# WCH_hairDrierBOTTOM_COM_V1_5.net
KiCad netlist of a schematic drawn in Altium Designer
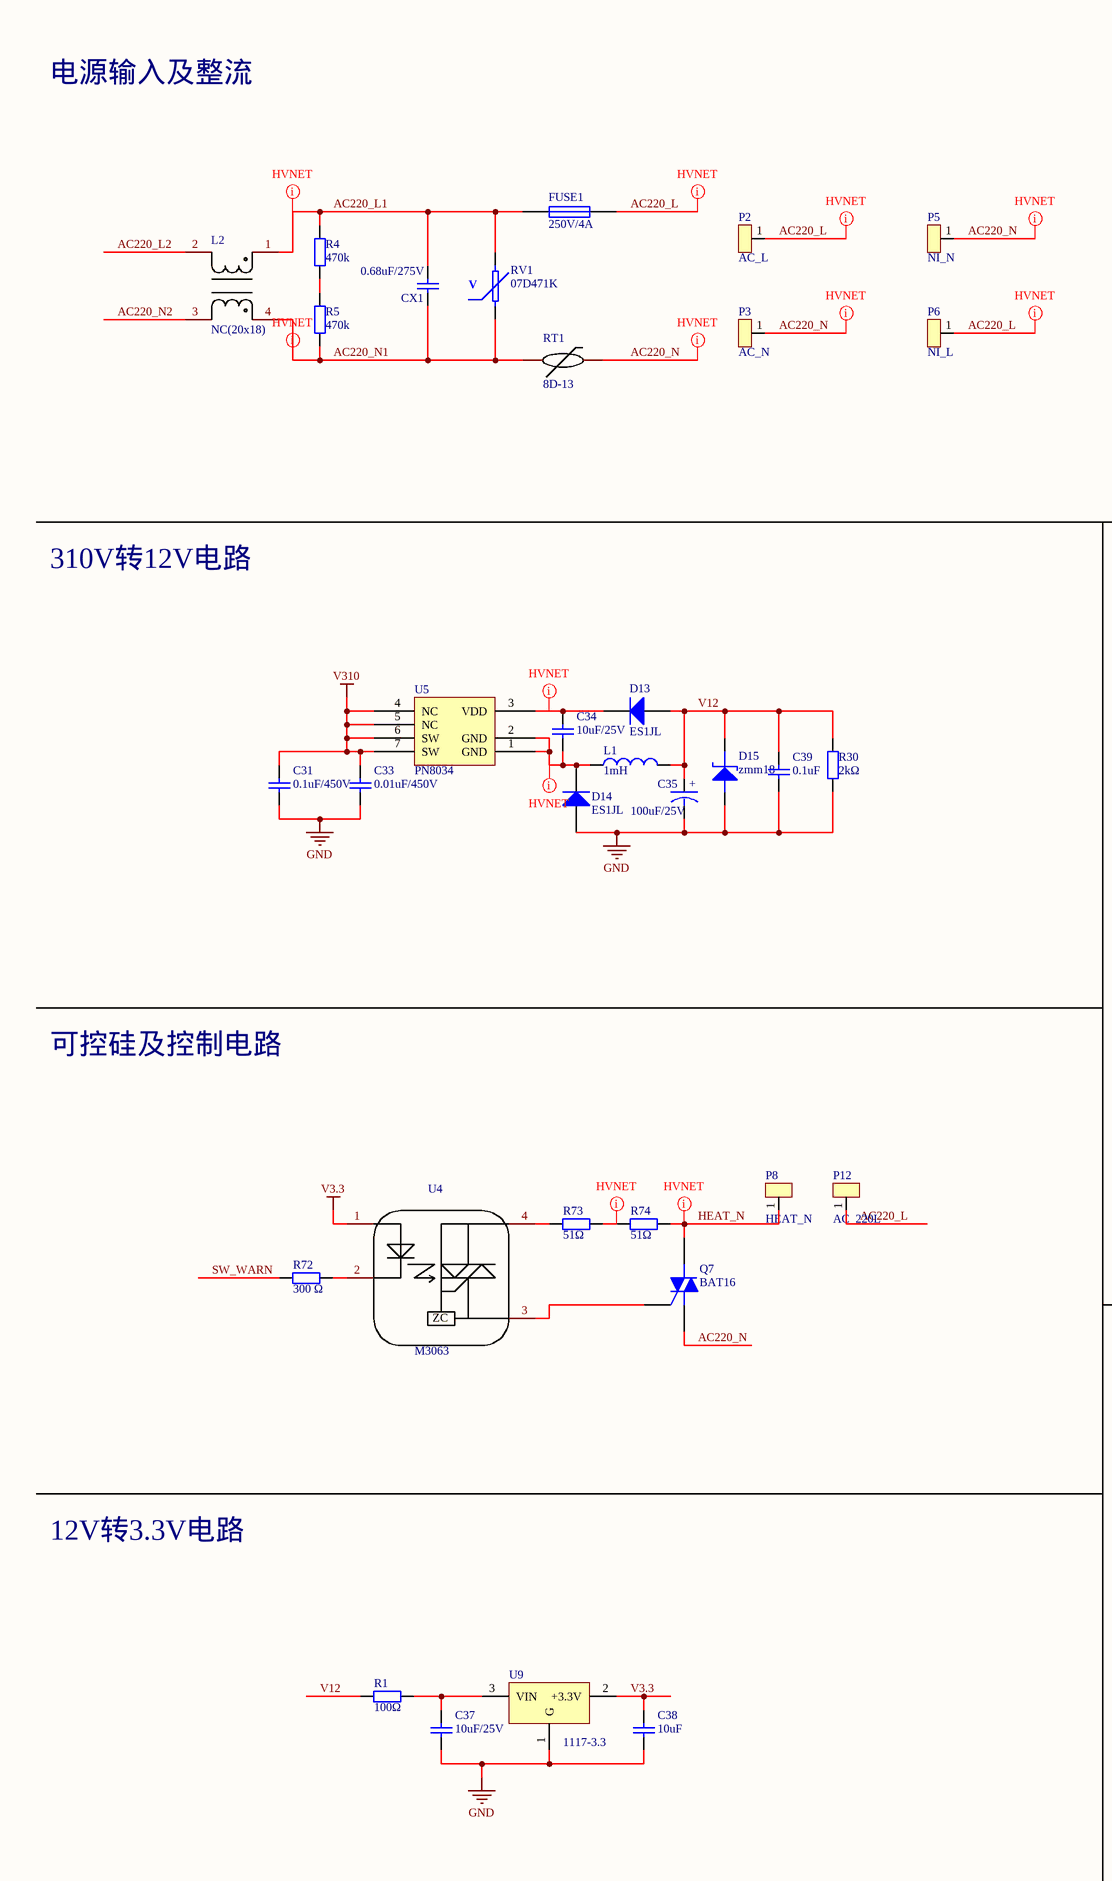
[diagram p0: WCH_hairDrierBOTTOM_COM_V1.5.SchDoc, left]
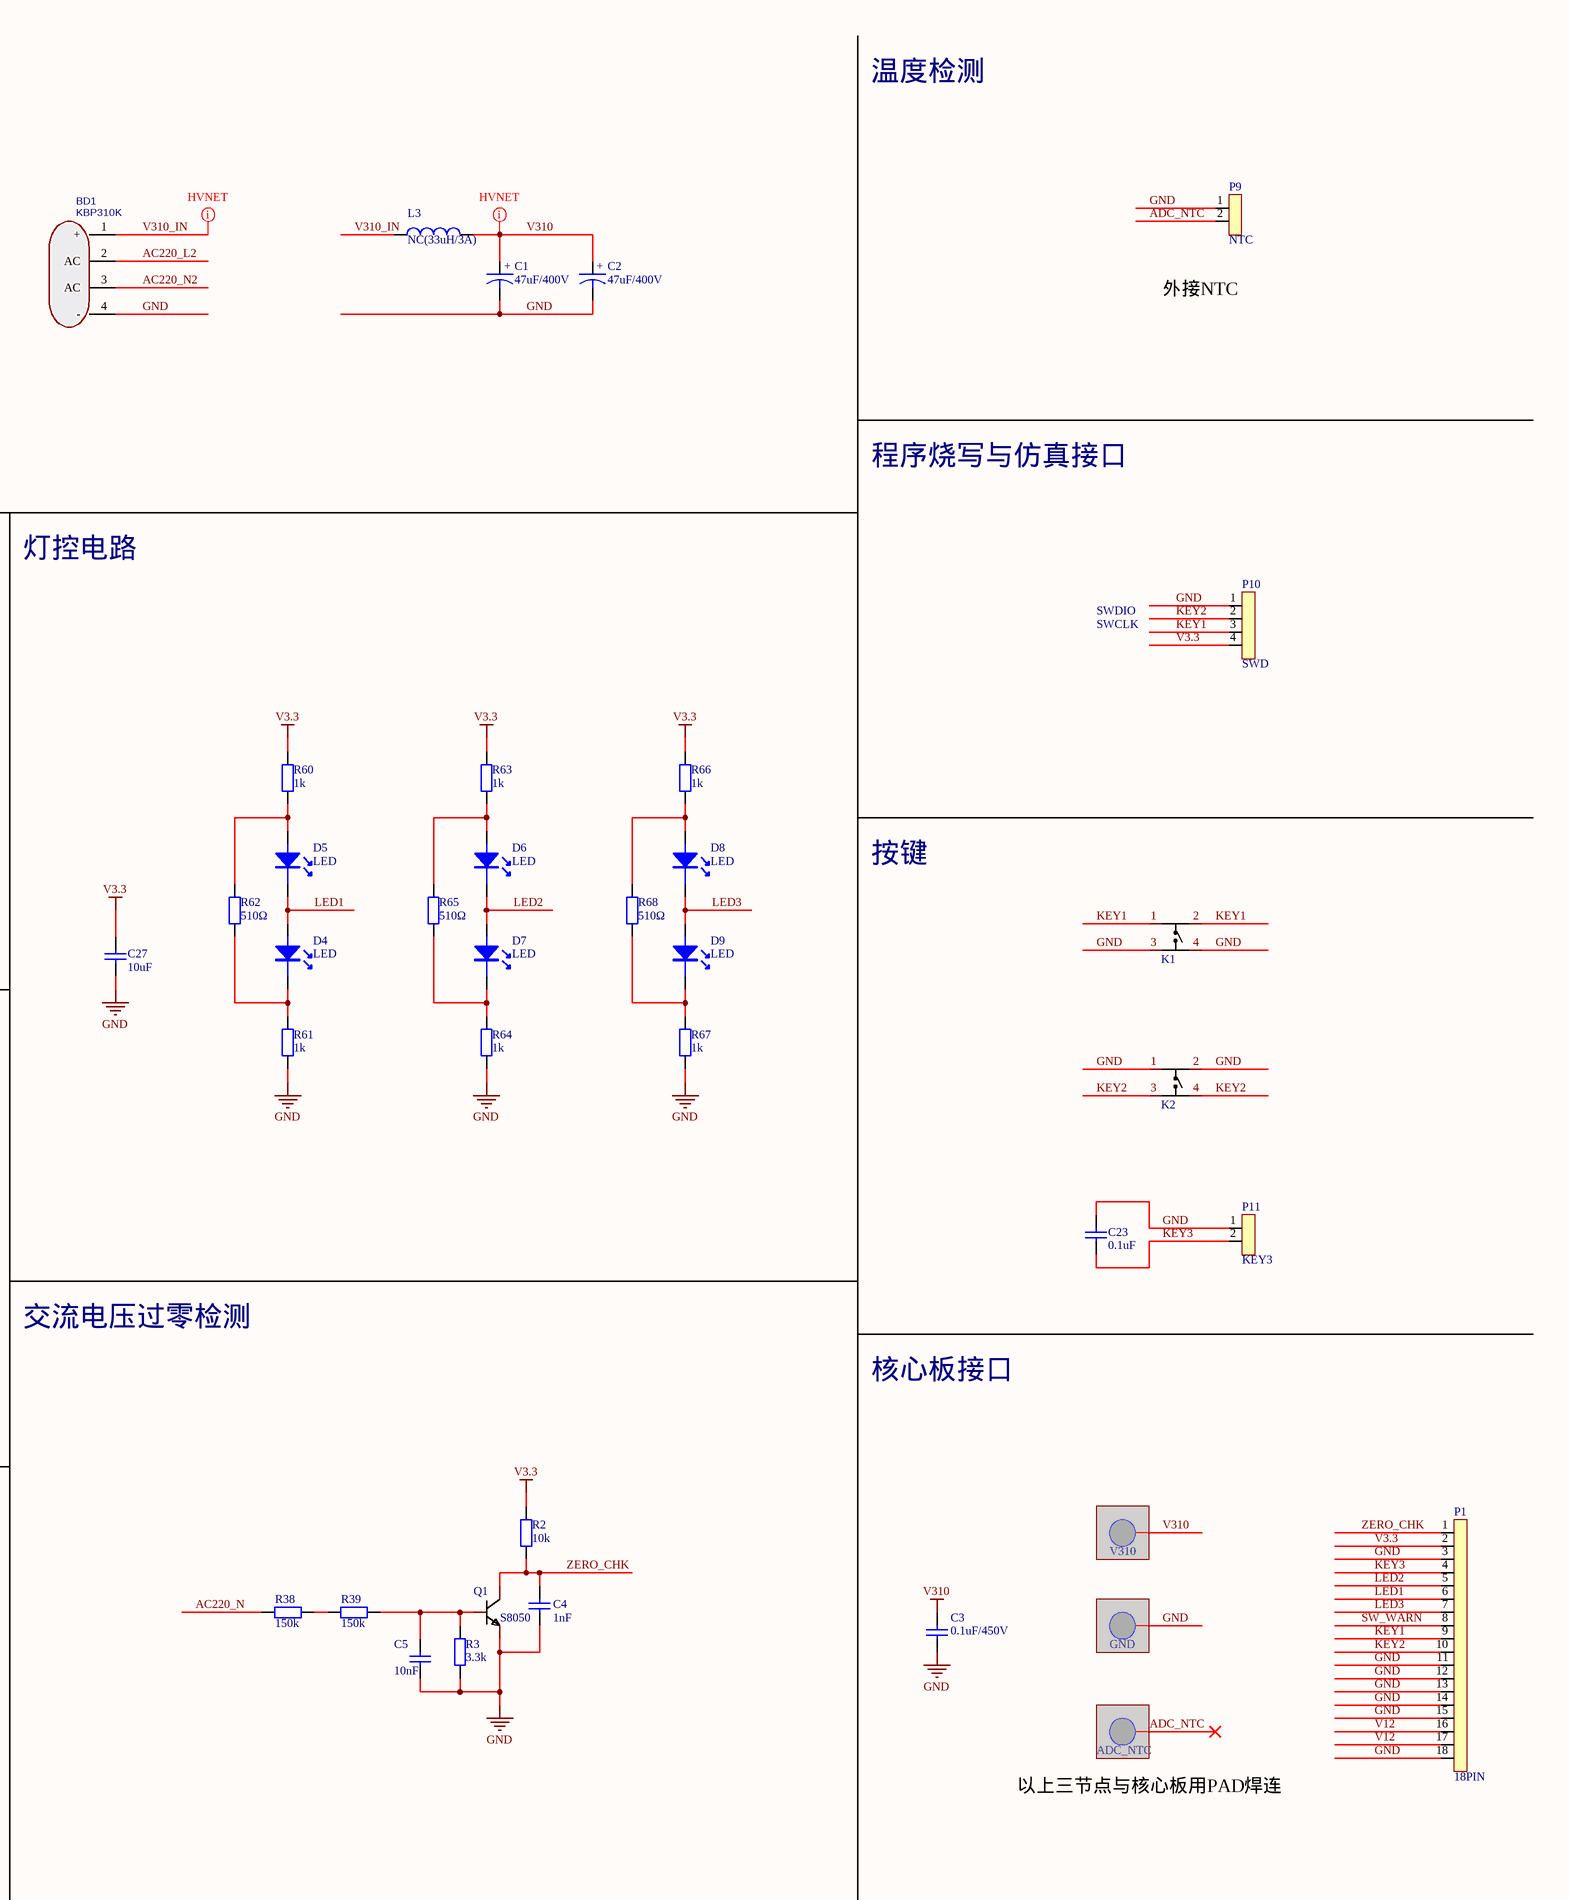
[diagram p1: WCH_hairDrierBOTTOM_COM_V1.5.SchDoc, right]

(export (version "E")
  (design (tool "Eeschema 10.0.6"))
  (components
    (comp (ref "BD1")
      (value "KBP310K")
      (footprint "3KBP")
      (fields (field (name "BOM_SUPPLIER PART") "C2496"))
      (libsource (lib "altium-import") (part "root_0_KBP310K_"))
    )
    (comp (ref "C1")
      (value "47uF/400V")
      (footprint "RB-.2/.4-M")
      (description "Capacitor")
      (libsource (lib "SMARTCORTEX M3-1700_1") (part "CAPACITOR POL_2"))
    )
    (comp (ref "C2")
      (value "47uF/400V")
      (footprint "RB-.2/.4-M")
      (description "Capacitor")
      (libsource (lib "SMARTCORTEX M3-1700_1") (part "CAPACITOR POL_2"))
    )
    (comp (ref "C3")
      (value "0.1uF/450V")
      (footprint "1206")
      (description "Capacitor (Semiconductor SIM Model)")
      (fields (field (name "PUBLISHER") "Altium Limited"))
      (libsource (lib "Miscellaneous Devices") (part "Cap Semi"))
    )
    (comp (ref "C4")
      (value "1nF")
      (footprint "M_C0402-")
      (description "Capacitor (Semiconductor SIM Model)")
      (fields (field (name "PUBLISHER") "Altium Limited"))
      (libsource (lib "Miscellaneous Devices") (part "Cap Semi"))
    )
    (comp (ref "C5")
      (value "10nF")
      (footprint "M_C0402-")
      (description "Capacitor (Semiconductor SIM Model)")
      (fields (field (name "PUBLISHER") "Altium Limited"))
      (libsource (lib "Miscellaneous Devices") (part "Cap Semi"))
    )
    (comp (ref "C23")
      (value "0.1uF")
      (footprint "M_C0402-")
      (description "Capacitor (Semiconductor SIM Model)")
      (fields (field (name "PUBLISHER") "Altium Limited"))
      (libsource (lib "Miscellaneous Devices") (part "Cap Semi"))
    )
    (comp (ref "C27")
      (value "10uF")
      (footprint "0603C")
      (description "Capacitor (Semiconductor SIM Model)")
      (fields (field (name "PUBLISHER") "Altium Limited"))
      (libsource (lib "Miscellaneous Devices") (part "Cap Semi"))
    )
    (comp (ref "C31")
      (value "0.1uF/450V")
      (footprint "1206")
      (description "Capacitor (Semiconductor SIM Model)")
      (fields (field (name "PUBLISHER") "Altium Limited"))
      (libsource (lib "Miscellaneous Devices") (part "Cap Semi"))
    )
    (comp (ref "C33")
      (value "0.01uF/450V")
      (footprint "1206")
      (description "Capacitor (Semiconductor SIM Model)")
      (fields (field (name "PUBLISHER") "Altium Limited"))
      (libsource (lib "Miscellaneous Devices") (part "Cap Semi"))
    )
    (comp (ref "C34")
      (value "10uF/25V")
      (footprint "0603C")
      (description "Capacitor (Semiconductor SIM Model)")
      (fields (field (name "PUBLISHER") "Altium Limited"))
      (libsource (lib "Miscellaneous Devices") (part "Cap Semi"))
    )
    (comp (ref "C35")
      (value "100uF/25V")
      (footprint "RB-.1/.2")
      (description "Capacitor")
      (libsource (lib "SMARTCORTEX M3-1700_1") (part "CAPACITOR POL_2"))
    )
    (comp (ref "C37")
      (value "10uF/25V")
      (footprint "0603C")
      (description "Capacitor (Semiconductor SIM Model)")
      (fields (field (name "PUBLISHER") "Altium Limited"))
      (libsource (lib "Miscellaneous Devices") (part "Cap Semi"))
    )
    (comp (ref "C38")
      (value "10uF")
      (footprint "0603C")
      (description "Capacitor (Semiconductor SIM Model)")
      (fields (field (name "PUBLISHER") "Altium Limited"))
      (libsource (lib "Miscellaneous Devices") (part "Cap Semi"))
    )
    (comp (ref "C39")
      (value "0.1uF")
      (footprint "M_C0402-")
      (description "Capacitor (Semiconductor SIM Model)")
      (fields (field (name "PUBLISHER") "Altium Limited"))
      (libsource (lib "Miscellaneous Devices") (part "Cap Semi"))
    )
    (comp (ref "CX1")
      (value "0.68uF/275V")
      (footprint "CAP-HV-10NF275V-680uf10mm")
      (description "Capacitor")
      (fields (field (name "PUBLISHER") "Altium Limited"))
      (libsource (lib "*") (part "Cap"))
    )
    (comp (ref "D4") (value "LED") (footprint "LED-0603") (libsource (lib "SUNWIN_SCH") (part "LED")))
    (comp (ref "D5") (value "LED") (footprint "LED-0603") (libsource (lib "SUNWIN_SCH") (part "LED")))
    (comp (ref "D6") (value "LED") (footprint "LED-0603") (libsource (lib "SUNWIN_SCH") (part "LED")))
    (comp (ref "D7") (value "LED") (footprint "LED-0603") (libsource (lib "SUNWIN_SCH") (part "LED")))
    (comp (ref "D8") (value "LED") (footprint "LED-0603") (libsource (lib "SUNWIN_SCH") (part "LED")))
    (comp (ref "D9") (value "LED") (footprint "LED-0603") (libsource (lib "SUNWIN_SCH") (part "LED")))
    (comp (ref "D13")
      (value "ES1JL")
      (footprint "SOD-123")
      (description "High Conductance Fast Diode")
      (fields (field (name "PUBLISHER") "Altium Limited"))
      (libsource (lib "Miscellaneous Devices") (part "Diode 1N4148"))
    )
    (comp (ref "D14")
      (value "ES1JL")
      (footprint "SOD-123")
      (description "High Conductance Fast Diode")
      (fields (field (name "PUBLISHER") "Altium Limited"))
      (libsource (lib "Miscellaneous Devices") (part "Diode 1N4148"))
    )
    (comp (ref "D15")
      (value "zmm18")
      (footprint "SOD-323")
      (libsource (lib "SUNWIN_SCH") (part "DIODE_ZENER"))
    )
    (comp (ref "FUSE1") (value "250V/4A") (footprint "FUSE_SMD") (libsource (lib "SUNWIN_SCH") (part "FUSE")))
    (comp (ref "K1")
      (value "KH-6X6X8H-STM")
      (footprint "KEY2-SMD")
      (libsource (lib "altium-import") (part "root_0_KH-6X6X8H-STM_"))
    )
    (comp (ref "K2")
      (value "KH-6X6X8H-STM")
      (footprint "KEY2-SMD")
      (libsource (lib "altium-import") (part "root_0_KH-6X6X8H-STM_"))
    )
    (comp (ref "L1")
      (value "1mH")
      (footprint "INDUCTOR-5040")
      (libsource (lib "SUNWIN_SCH") (part "INDUCTOR"))
    )
    (comp (ref "L2")
      (value "NC(20x18)")
      (footprint "M_COMM_INDUCTOR11*8")
      (fields (field (name "MANUFACTURER PART") "UU9.8-5mH"))
      (libsource (lib "altium-import") (part "root_0_mirrored_UU9.8-5mH_"))
    )
    (comp (ref "L3")
      (value "NC(33uH/3A)")
      (footprint "INDUCTOR PCMC063T")
      (libsource (lib "SUNWIN_SCH") (part "INDUCTOR"))
    )
    (comp (ref "P1") (value "18PIN") (footprint "P1.27-18-SMD") (libsource (lib "SUNWIN_SCH") (part "18PIN")))
    (comp (ref "P2")
      (value "AC_L")
      (footprint "PAD-1.2/2")
      (description "CONNECTOR")
      (libsource (lib "") (part "1PIN_1"))
    )
    (comp (ref "P3")
      (value "AC_N")
      (footprint "PAD-1.2/2")
      (description "CONNECTOR")
      (libsource (lib "") (part "1PIN_1"))
    )
    (comp (ref "P5")
      (value "NI_N")
      (footprint "PAD-1.2/2")
      (description "CONNECTOR")
      (libsource (lib "") (part "1PIN_1"))
    )
    (comp (ref "P6")
      (value "NI_L")
      (footprint "PAD-1.2/2")
      (description "CONNECTOR")
      (libsource (lib "") (part "1PIN_1"))
    )
    (comp (ref "P8")
      (value "HEAT_N")
      (footprint "PAD-1.2/2")
      (description "CONNECTOR")
      (libsource (lib "SUNWIN_SCH") (part "1PIN"))
    )
    (comp (ref "P9") (value "NTC") (footprint "GH1.25-2P") (libsource (lib "SUNWIN_SCH") (part "2PIN")))
    (comp (ref "P10") (value "SWD") (footprint "2510-4") (libsource (lib "SUNWIN_SCH") (part "4PIN")))
    (comp (ref "P11") (value "KEY3") (footprint "GH1.25-2P") (libsource (lib "SUNWIN_SCH") (part "2PIN")))
    (comp (ref "P12")
      (value "AC_220L")
      (footprint "PAD-1.2/2")
      (description "CONNECTOR")
      (libsource (lib "SUNWIN_SCH") (part "1PIN"))
    )
    (comp (ref "Q1")
      (value "S8050")
      (footprint "SOT-23")
      (libsource (lib "altium-import") (part "root_0_S8050_C105433_"))
    )
    (comp (ref "Q7")
      (value "BAT16")
      (footprint "M_TO220_2")
      (description "Silicon Bidirectional Triode Thyristor")
      (fields (field (name "PUBLISHER") "Altium Limited"))
      (libsource (lib "Miscellaneous Devices") (part "Triac"))
    )
    (comp (ref "R1")
      (value "100Ω")
      (footprint "1206-")
      (description "Resistor")
      (fields (field (name "PUBLISHER") "Altium Limited"))
      (libsource (lib "") (part "Res2_1"))
    )
    (comp (ref "R2")
      (value "10k")
      (footprint "M_R0402")
      (description "Resistor")
      (fields (field (name "PUBLISHER") "Altium Limited"))
      (libsource (lib "Miscellaneous Devices") (part "Res2"))
    )
    (comp (ref "R3")
      (value "3.3k")
      (footprint "M_R0402")
      (description "Resistor")
      (fields (field (name "PUBLISHER") "Altium Limited"))
      (libsource (lib "") (part "Res2_2"))
    )
    (comp (ref "R4")
      (value "470k")
      (footprint "1206-")
      (description "Resistor")
      (fields (field (name "PUBLISHER") "Altium Limited"))
      (libsource (lib "Miscellaneous Devices") (part "Res2"))
    )
    (comp (ref "R5")
      (value "470k")
      (footprint "1206-")
      (description "Resistor")
      (fields (field (name "PUBLISHER") "Altium Limited"))
      (libsource (lib "Miscellaneous Devices") (part "Res2"))
    )
    (comp (ref "R30")
      (value "2kΩ")
      (footprint "0805")
      (description "Resistor")
      (fields (field (name "PUBLISHER") "Altium Limited"))
      (libsource (lib "") (part "Res2_2"))
    )
    (comp (ref "R38")
      (value "150k")
      (footprint "1206-")
      (description "Resistor")
      (fields (field (name "PUBLISHER") "Altium Limited"))
      (libsource (lib "") (part "Res2_1"))
    )
    (comp (ref "R39")
      (value "150k")
      (footprint "1206-")
      (description "Resistor")
      (fields (field (name "PUBLISHER") "Altium Limited"))
      (libsource (lib "") (part "Res2_1"))
    )
    (comp (ref "R60")
      (value "1k")
      (footprint "0603")
      (description "Resistor")
      (fields (field (name "PUBLISHER") "Altium Limited"))
      (libsource (lib "") (part "Res2_2"))
    )
    (comp (ref "R61")
      (value "1k")
      (footprint "0603")
      (description "Resistor")
      (fields (field (name "PUBLISHER") "Altium Limited"))
      (libsource (lib "Miscellaneous Devices") (part "Res2"))
    )
    (comp (ref "R62")
      (value "510Ω")
      (footprint "0603")
      (description "Resistor")
      (fields (field (name "PUBLISHER") "Altium Limited"))
      (libsource (lib "Miscellaneous Devices") (part "Res2"))
    )
    (comp (ref "R63")
      (value "1k")
      (footprint "0603")
      (description "Resistor")
      (fields (field (name "PUBLISHER") "Altium Limited"))
      (libsource (lib "") (part "Res2_2"))
    )
    (comp (ref "R64")
      (value "1k")
      (footprint "0603")
      (description "Resistor")
      (fields (field (name "PUBLISHER") "Altium Limited"))
      (libsource (lib "Miscellaneous Devices") (part "Res2"))
    )
    (comp (ref "R65")
      (value "510Ω")
      (footprint "0603")
      (description "Resistor")
      (fields (field (name "PUBLISHER") "Altium Limited"))
      (libsource (lib "Miscellaneous Devices") (part "Res2"))
    )
    (comp (ref "R66")
      (value "1k")
      (footprint "0603")
      (description "Resistor")
      (fields (field (name "PUBLISHER") "Altium Limited"))
      (libsource (lib "") (part "Res2_2"))
    )
    (comp (ref "R67")
      (value "1k")
      (footprint "0603")
      (description "Resistor")
      (fields (field (name "PUBLISHER") "Altium Limited"))
      (libsource (lib "Miscellaneous Devices") (part "Res2"))
    )
    (comp (ref "R68")
      (value "510Ω")
      (footprint "0603")
      (description "Resistor")
      (fields (field (name "PUBLISHER") "Altium Limited"))
      (libsource (lib "Miscellaneous Devices") (part "Res2"))
    )
    (comp (ref "R72")
      (value "300 Ω")
      (footprint "0603")
      (description "Resistor")
      (fields (field (name "PUBLISHER") "Altium Limited"))
      (libsource (lib "") (part "Res2_1"))
    )
    (comp (ref "R73")
      (value "51Ω")
      (footprint "1206-")
      (description "Resistor")
      (fields (field (name "PUBLISHER") "Altium Limited"))
      (libsource (lib "") (part "Res2_1"))
    )
    (comp (ref "R74")
      (value "51Ω")
      (footprint "1206-")
      (description "Resistor")
      (fields (field (name "PUBLISHER") "Altium Limited"))
      (libsource (lib "") (part "Res2_1"))
    )
    (comp (ref "RT1")
      (value "8D-13")
      (footprint "RT_5D")
      (fields (field (name "MANUFACTURER PART") "NTC 5D-11"))
      (libsource (lib "altium-import") (part "root_2_NTC 5D-11_"))
    )
    (comp (ref "RV1") (value "07D471K") (footprint "7D391") (libsource (lib "SUNWIN_SCH") (part "RV")))
    (comp (ref "U4")
      (value "M3063")
      (footprint "SOP-4_L3.8-W4.6-H2.0-LS7.0-P2.54")
      (fields (field (name "MANUFACTURER PART") "FODM3063"))
      (libsource (lib "altium-import") (part "root_0_FODM3063_"))
    )
    (comp (ref "U5")
      (value "PN8034")
      (footprint "SOP-7")
      (libsource (lib "altium-import") (part "root_0_PN8054_"))
    )
    (comp (ref "U9") (value "1117-3.3") (footprint "SOT-89") (libsource (lib "SUNWIN_SCH") (part "1117-3.3")))
  )
  (nets
    (net (code "1") (name "/AC220_L") (class "Default")
      (node (ref "FUSE1") (pin "2") (pinfunction "2_2") (pintype "passive"))
      (node (ref "P12") (pin "1") (pintype "passive"))
      (node (ref "P2") (pin "1") (pintype "passive"))
      (node (ref "P6") (pin "1") (pintype "passive"))
    )
    (net (code "2") (name "/AC220_L1") (class "Default")
      (node (ref "CX1") (pin "1") (pinfunction "1_1") (pintype "passive"))
      (node (ref "FUSE1") (pin "1") (pinfunction "1_1") (pintype "passive"))
      (node (ref "L2") (pin "1") (pinfunction "1_1") (pintype "passive"))
      (node (ref "R4") (pin "1") (pinfunction "1_1") (pintype "passive"))
      (node (ref "RV1") (pin "2") (pinfunction "2_2") (pintype "passive"))
    )
    (net (code "3") (name "/AC220_L2") (class "Default")
      (node (ref "BD1") (pin "2") (pinfunction "AC_2") (pintype "passive"))
      (node (ref "L2") (pin "2") (pinfunction "2_2") (pintype "passive"))
    )
    (net (code "4") (name "/AC220_N") (class "Default")
      (node (ref "P3") (pin "1") (pintype "passive"))
      (node (ref "P5") (pin "1") (pintype "passive"))
      (node (ref "Q7") (pin "1") (pinfunction "M1_1") (pintype "passive"))
      (node (ref "R38") (pin "2") (pinfunction "2_2") (pintype "passive"))
      (node (ref "RT1") (pin "1") (pinfunction "1_1") (pintype "passive"))
    )
    (net (code "5") (name "/AC220_N1") (class "Default")
      (node (ref "CX1") (pin "2") (pinfunction "2_2") (pintype "passive"))
      (node (ref "L2") (pin "4") (pinfunction "4_4") (pintype "passive"))
      (node (ref "R5") (pin "2") (pinfunction "2_2") (pintype "passive"))
      (node (ref "RT1") (pin "2") (pinfunction "2_2") (pintype "passive"))
      (node (ref "RV1") (pin "1") (pinfunction "1_1") (pintype "passive"))
    )
    (net (code "6") (name "/AC220_N2") (class "Default")
      (node (ref "BD1") (pin "3") (pinfunction "AC_3") (pintype "passive"))
      (node (ref "L2") (pin "3") (pinfunction "3_3") (pintype "passive"))
    )
    (net (code "7") (name "/ADC_NTC") (class "Default")
      (node (ref "P9") (pin "2") (pintype "passive+no_connect"))
    )
    (net (code "8") (name "/HEAT_N") (class "Default")
      (node (ref "P8") (pin "1") (pintype "passive"))
      (node (ref "Q7") (pin "2") (pinfunction "M2_2") (pintype "passive"))
      (node (ref "R74") (pin "1") (pinfunction "1_1") (pintype "passive"))
    )
    (net (code "9") (name "/KEY1") (class "Default")
      (node (ref "K1") (pin "1") (pinfunction "A_1") (pintype "passive"))
      (node (ref "K1") (pin "2") (pinfunction "B_2") (pintype "passive"))
      (node (ref "P1") (pin "9") (pintype "passive"))
      (node (ref "P10") (pin "3") (pintype "passive"))
    )
    (net (code "10") (name "/KEY2") (class "Default")
      (node (ref "K2") (pin "3") (pinfunction "C_3") (pintype "passive"))
      (node (ref "K2") (pin "4") (pinfunction "D_4") (pintype "passive"))
      (node (ref "P1") (pin "10") (pintype "passive"))
      (node (ref "P10") (pin "2") (pintype "passive"))
    )
    (net (code "11") (name "/KEY3") (class "Default")
      (node (ref "C23") (pin "1") (pinfunction "1_1") (pintype "passive"))
      (node (ref "P1") (pin "4") (pintype "passive"))
      (node (ref "P11") (pin "2") (pintype "passive"))
    )
    (net (code "12") (name "/LED1") (class "Default")
      (node (ref "D4") (pin "1") (pinfunction "A_1") (pintype "passive"))
      (node (ref "D5") (pin "2") (pinfunction "K_2") (pintype "passive"))
      (node (ref "P1") (pin "6") (pintype "passive"))
    )
    (net (code "13") (name "/LED2") (class "Default")
      (node (ref "D6") (pin "2") (pinfunction "K_2") (pintype "passive"))
      (node (ref "D7") (pin "1") (pinfunction "A_1") (pintype "passive"))
      (node (ref "P1") (pin "5") (pintype "passive"))
    )
    (net (code "14") (name "/LED3") (class "Default")
      (node (ref "D8") (pin "2") (pinfunction "K_2") (pintype "passive"))
      (node (ref "D9") (pin "1") (pinfunction "A_1") (pintype "passive"))
      (node (ref "P1") (pin "7") (pintype "passive"))
    )
    (net (code "15") (name "/SW_WARN") (class "Default")
      (node (ref "P1") (pin "8") (pintype "passive"))
      (node (ref "R72") (pin "2") (pinfunction "2_2") (pintype "passive"))
    )
    (net (code "16") (name "/V12") (class "Default")
      (node (ref "C35") (pin "1") (pinfunction "1_1") (pintype "passive"))
      (node (ref "C39") (pin "1") (pinfunction "1_1") (pintype "passive"))
      (node (ref "D13") (pin "1") (pinfunction "A_1") (pintype "passive"))
      (node (ref "D15") (pin "2") (pinfunction "K_2") (pintype "passive"))
      (node (ref "L1") (pin "2") (pinfunction "2_2") (pintype "passive"))
      (node (ref "P1") (pin "16") (pintype "passive"))
      (node (ref "P1") (pin "17") (pintype "passive"))
      (node (ref "R1") (pin "2") (pinfunction "2_2") (pintype "passive"))
      (node (ref "R30") (pin "2") (pinfunction "2_2") (pintype "passive"))
    )
    (net (code "17") (name "/V310_IN") (class "Default")
      (node (ref "BD1") (pin "1") (pinfunction "+_1") (pintype "passive"))
      (node (ref "L3") (pin "1") (pinfunction "1_1") (pintype "passive"))
    )
    (net (code "18") (name "/ZERO_CHK") (class "Default")
      (node (ref "C4") (pin "1") (pinfunction "1_1") (pintype "passive"))
      (node (ref "P1") (pin "1") (pintype "passive"))
      (node (ref "Q1") (pin "3") (pinfunction "3_3") (pintype "passive"))
      (node (ref "R2") (pin "2") (pinfunction "2_2") (pintype "passive"))
    )
    (net (code "19") (name "GND") (class "Default")
      (node (ref "BD1") (pin "4") (pinfunction "-_4") (pintype "passive"))
      (node (ref "C1") (pin "2") (pinfunction "2_2") (pintype "passive"))
      (node (ref "C2") (pin "2") (pinfunction "2_2") (pintype "passive"))
      (node (ref "C23") (pin "2") (pinfunction "2_2") (pintype "passive"))
      (node (ref "C27") (pin "2") (pinfunction "2_2") (pintype "passive"))
      (node (ref "C3") (pin "2") (pinfunction "2_2") (pintype "passive"))
      (node (ref "C31") (pin "2") (pinfunction "2_2") (pintype "passive"))
      (node (ref "C33") (pin "2") (pinfunction "2_2") (pintype "passive"))
      (node (ref "C35") (pin "2") (pinfunction "2_2") (pintype "passive"))
      (node (ref "C37") (pin "2") (pinfunction "2_2") (pintype "passive"))
      (node (ref "C38") (pin "2") (pinfunction "2_2") (pintype "passive"))
      (node (ref "C39") (pin "2") (pinfunction "2_2") (pintype "passive"))
      (node (ref "C4") (pin "2") (pinfunction "2_2") (pintype "passive"))
      (node (ref "C5") (pin "2") (pinfunction "2_2") (pintype "passive"))
      (node (ref "D14") (pin "1") (pinfunction "A_1") (pintype "passive"))
      (node (ref "D15") (pin "1") (pinfunction "A_1") (pintype "passive"))
      (node (ref "K1") (pin "3") (pinfunction "C_3") (pintype "passive"))
      (node (ref "K1") (pin "4") (pinfunction "D_4") (pintype "passive"))
      (node (ref "K2") (pin "1") (pinfunction "A_1") (pintype "passive"))
      (node (ref "K2") (pin "2") (pinfunction "B_2") (pintype "passive"))
      (node (ref "P1") (pin "11") (pintype "passive"))
      (node (ref "P1") (pin "12") (pintype "passive"))
      (node (ref "P1") (pin "13") (pintype "passive"))
      (node (ref "P1") (pin "14") (pintype "passive"))
      (node (ref "P1") (pin "15") (pintype "passive"))
      (node (ref "P1") (pin "18") (pintype "passive"))
      (node (ref "P1") (pin "3") (pintype "passive"))
      (node (ref "P10") (pin "1") (pintype "passive"))
      (node (ref "P11") (pin "1") (pintype "passive"))
      (node (ref "P9") (pin "1") (pintype "passive"))
      (node (ref "Q1") (pin "2") (pinfunction "2_2") (pintype "passive"))
      (node (ref "R3") (pin "1") (pinfunction "1_1") (pintype "passive"))
      (node (ref "R30") (pin "1") (pinfunction "1_1") (pintype "passive"))
      (node (ref "R61") (pin "2") (pinfunction "2_2") (pintype "passive"))
      (node (ref "R64") (pin "2") (pinfunction "2_2") (pintype "passive"))
      (node (ref "R67") (pin "2") (pinfunction "2_2") (pintype "passive"))
      (node (ref "U9") (pin "1") (pinfunction "G_1") (pintype "passive"))
    )
    (net (code "20") (name "Net-(C5-Pad1)") (class "Default")
      (node (ref "C5") (pin "1") (pinfunction "1_1") (pintype "passive"))
      (node (ref "Q1") (pin "1") (pinfunction "1_1") (pintype "passive"))
      (node (ref "R3") (pin "2") (pinfunction "2_2") (pintype "passive"))
      (node (ref "R39") (pin "1") (pinfunction "1_1") (pintype "passive"))
    )
    (net (code "21") (name "Net-(D4-K)") (class "Default")
      (node (ref "D4") (pin "2") (pinfunction "K_2") (pintype "passive"))
      (node (ref "R61") (pin "1") (pinfunction "1_1") (pintype "passive"))
      (node (ref "R62") (pin "2") (pinfunction "2_2") (pintype "passive"))
    )
    (net (code "22") (name "Net-(D5-A)") (class "Default")
      (node (ref "D5") (pin "1") (pinfunction "A_1") (pintype "passive"))
      (node (ref "R60") (pin "1") (pinfunction "1_1") (pintype "passive"))
      (node (ref "R62") (pin "1") (pinfunction "1_1") (pintype "passive"))
    )
    (net (code "23") (name "Net-(D6-A)") (class "Default")
      (node (ref "D6") (pin "1") (pinfunction "A_1") (pintype "passive"))
      (node (ref "R63") (pin "1") (pinfunction "1_1") (pintype "passive"))
      (node (ref "R65") (pin "1") (pinfunction "1_1") (pintype "passive"))
    )
    (net (code "24") (name "Net-(D7-K)") (class "Default")
      (node (ref "D7") (pin "2") (pinfunction "K_2") (pintype "passive"))
      (node (ref "R64") (pin "1") (pinfunction "1_1") (pintype "passive"))
      (node (ref "R65") (pin "2") (pinfunction "2_2") (pintype "passive"))
    )
    (net (code "25") (name "Net-(D8-A)") (class "Default")
      (node (ref "D8") (pin "1") (pinfunction "A_1") (pintype "passive"))
      (node (ref "R66") (pin "1") (pinfunction "1_1") (pintype "passive"))
      (node (ref "R68") (pin "1") (pinfunction "1_1") (pintype "passive"))
    )
    (net (code "26") (name "Net-(D9-K)") (class "Default")
      (node (ref "D9") (pin "2") (pinfunction "K_2") (pintype "passive"))
      (node (ref "R67") (pin "1") (pinfunction "1_1") (pintype "passive"))
      (node (ref "R68") (pin "2") (pinfunction "2_2") (pintype "passive"))
    )
    (net (code "27") (name "Net-(D13-K)") (class "Default")
      (node (ref "C34") (pin "1") (pinfunction "1_1") (pintype "passive"))
      (node (ref "D13") (pin "2") (pinfunction "K_2") (pintype "passive"))
      (node (ref "U5") (pin "3") (pinfunction "VDD_3") (pintype "passive"))
    )
    (net (code "28") (name "Net-(D14-K)") (class "Default")
      (node (ref "C34") (pin "2") (pinfunction "2_2") (pintype "passive"))
      (node (ref "D14") (pin "2") (pinfunction "K_2") (pintype "passive"))
      (node (ref "L1") (pin "1") (pinfunction "1_1") (pintype "passive"))
      (node (ref "U5") (pin "1") (pinfunction "GND_1") (pintype "passive"))
      (node (ref "U5") (pin "2") (pinfunction "GND_2") (pintype "passive"))
    )
    (net (code "29") (name "Net-(Q7-G)") (class "Default")
      (node (ref "Q7") (pin "3") (pinfunction "G_3") (pintype "passive"))
      (node (ref "U4") (pin "3") (pinfunction "3_3") (pintype "passive"))
    )
    (net (code "30") (name "Net-(R4-Pad2)") (class "Default")
      (node (ref "R4") (pin "2") (pinfunction "2_2") (pintype "passive"))
      (node (ref "R5") (pin "1") (pinfunction "1_1") (pintype "passive"))
    )
    (net (code "31") (name "Net-(R38-Pad1)") (class "Default")
      (node (ref "R38") (pin "1") (pinfunction "1_1") (pintype "passive"))
      (node (ref "R39") (pin "2") (pinfunction "2_2") (pintype "passive"))
    )
    (net (code "32") (name "Net-(R72-Pad1)") (class "Default")
      (node (ref "R72") (pin "1") (pinfunction "1_1") (pintype "passive"))
      (node (ref "U4") (pin "2") (pinfunction "2_2") (pintype "passive"))
    )
    (net (code "33") (name "Net-(R73-Pad1)") (class "Default")
      (node (ref "R73") (pin "1") (pinfunction "1_1") (pintype "passive"))
      (node (ref "R74") (pin "2") (pinfunction "2_2") (pintype "passive"))
    )
    (net (code "34") (name "Net-(R73-Pad2)") (class "Default")
      (node (ref "R73") (pin "2") (pinfunction "2_2") (pintype "passive"))
      (node (ref "U4") (pin "4") (pinfunction "4_4") (pintype "passive"))
    )
    (net (code "35") (name "Net-(U9-VIN)") (class "Default")
      (node (ref "C37") (pin "1") (pinfunction "1_1") (pintype "passive"))
      (node (ref "R1") (pin "1") (pinfunction "1_1") (pintype "passive"))
      (node (ref "U9") (pin "3") (pinfunction "VIN_3") (pintype "passive"))
    )
    (net (code "36") (name "V3.3") (class "Default")
      (node (ref "C27") (pin "1") (pinfunction "1_1") (pintype "passive"))
      (node (ref "C38") (pin "1") (pinfunction "1_1") (pintype "passive"))
      (node (ref "P1") (pin "2") (pintype "passive"))
      (node (ref "P10") (pin "4") (pintype "passive"))
      (node (ref "R2") (pin "1") (pinfunction "1_1") (pintype "passive"))
      (node (ref "R60") (pin "2") (pinfunction "2_2") (pintype "passive"))
      (node (ref "R63") (pin "2") (pinfunction "2_2") (pintype "passive"))
      (node (ref "R66") (pin "2") (pinfunction "2_2") (pintype "passive"))
      (node (ref "U4") (pin "1") (pinfunction "1_1") (pintype "passive"))
      (node (ref "U9") (pin "2") (pinfunction "+3.3V_2") (pintype "passive"))
    )
    (net (code "37") (name "V310") (class "Default")
      (node (ref "C1") (pin "1") (pinfunction "1_1") (pintype "passive"))
      (node (ref "C2") (pin "1") (pinfunction "1_1") (pintype "passive"))
      (node (ref "C3") (pin "1") (pinfunction "1_1") (pintype "passive"))
      (node (ref "C31") (pin "1") (pinfunction "1_1") (pintype "passive"))
      (node (ref "C33") (pin "1") (pinfunction "1_1") (pintype "passive"))
      (node (ref "L3") (pin "2") (pinfunction "2_2") (pintype "passive"))
      (node (ref "U5") (pin "4") (pinfunction "NC_4") (pintype "passive"))
      (node (ref "U5") (pin "5") (pinfunction "NC_5") (pintype "passive"))
      (node (ref "U5") (pin "6") (pinfunction "SW_6") (pintype "passive"))
      (node (ref "U5") (pin "7") (pinfunction "SW_7") (pintype "passive"))
    )
  )
)
